# controller_tap.net
KiCad netlist of a schematic drawn in EAGLE
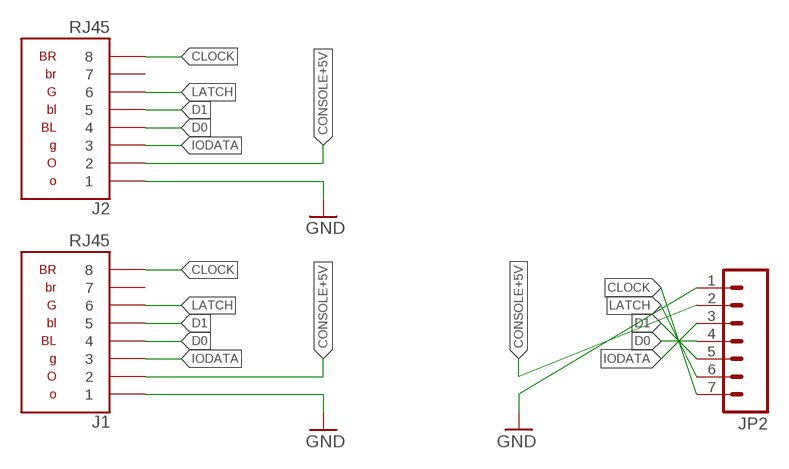
[diagram p0: schematic, sheet 1]

(export (version "E")
  (design (tool "Eeschema 10.0.6"))
  (components
    (comp (ref "J1")
      (value "RJ45")
      (footprint "eagle-import:RJ45")
      (libsource (lib "eagle-import") (part "RJ45"))
    )
    (comp (ref "J2")
      (value "RJ45")
      (footprint "eagle-import:RJ45")
      (libsource (lib "eagle-import") (part "RJ45"))
    )
    (comp (ref "JP2")
      (value "M07")
      (footprint "eagle-import:1X07")
      (libsource (lib "eagle-import") (part "M07"))
    )
  )
  (nets
    (net (code "1") (name "CLOCK") (class "Default")
      (node (ref "J1") (pin "8") (pinfunction "8_8") (pintype "bidirectional"))
      (node (ref "J2") (pin "8") (pinfunction "8_8") (pintype "bidirectional"))
      (node (ref "JP2") (pin "7") (pinfunction "7_7") (pintype "passive"))
    )
    (net (code "2") (name "CONSOLE+5V") (class "Default")
      (node (ref "J1") (pin "2") (pinfunction "2_2") (pintype "bidirectional"))
      (node (ref "J2") (pin "2") (pinfunction "2_2") (pintype "bidirectional"))
      (node (ref "JP2") (pin "2") (pinfunction "2_2") (pintype "passive"))
    )
    (net (code "3") (name "D0") (class "Default")
      (node (ref "J1") (pin "4") (pinfunction "4_4") (pintype "bidirectional"))
      (node (ref "J2") (pin "4") (pinfunction "4_4") (pintype "bidirectional"))
      (node (ref "JP2") (pin "4") (pinfunction "4_4") (pintype "passive"))
    )
    (net (code "4") (name "D1") (class "Default")
      (node (ref "J1") (pin "5") (pinfunction "5_5") (pintype "bidirectional"))
      (node (ref "J2") (pin "5") (pinfunction "5_5") (pintype "bidirectional"))
      (node (ref "JP2") (pin "5") (pinfunction "5_5") (pintype "passive"))
    )
    (net (code "5") (name "GND") (class "Default")
      (node (ref "J1") (pin "1") (pinfunction "1_1") (pintype "bidirectional"))
      (node (ref "J2") (pin "1") (pinfunction "1_1") (pintype "bidirectional"))
      (node (ref "JP2") (pin "1") (pinfunction "1_1") (pintype "passive"))
    )
    (net (code "6") (name "IODATA") (class "Default")
      (node (ref "J1") (pin "3") (pinfunction "3_3") (pintype "bidirectional"))
      (node (ref "J2") (pin "3") (pinfunction "3_3") (pintype "bidirectional"))
      (node (ref "JP2") (pin "3") (pinfunction "3_3") (pintype "passive"))
    )
    (net (code "7") (name "LATCH") (class "Default")
      (node (ref "J1") (pin "6") (pinfunction "6_6") (pintype "bidirectional"))
      (node (ref "J2") (pin "6") (pinfunction "6_6") (pintype "bidirectional"))
      (node (ref "JP2") (pin "6") (pinfunction "6_6") (pintype "passive"))
    )
    (net (code "8") (name "unconnected-(J1-Pad7)") (class "Default")
      (node (ref "J1") (pin "7") (pinfunction "7_7") (pintype "bidirectional"))
    )
    (net (code "9") (name "unconnected-(J2-Pad7)") (class "Default")
      (node (ref "J2") (pin "7") (pinfunction "7_7") (pintype "bidirectional"))
    )
  )
)
